# Arduino_Lego_Tank.net
KiCad netlist of a schematic drawn in EAGLE
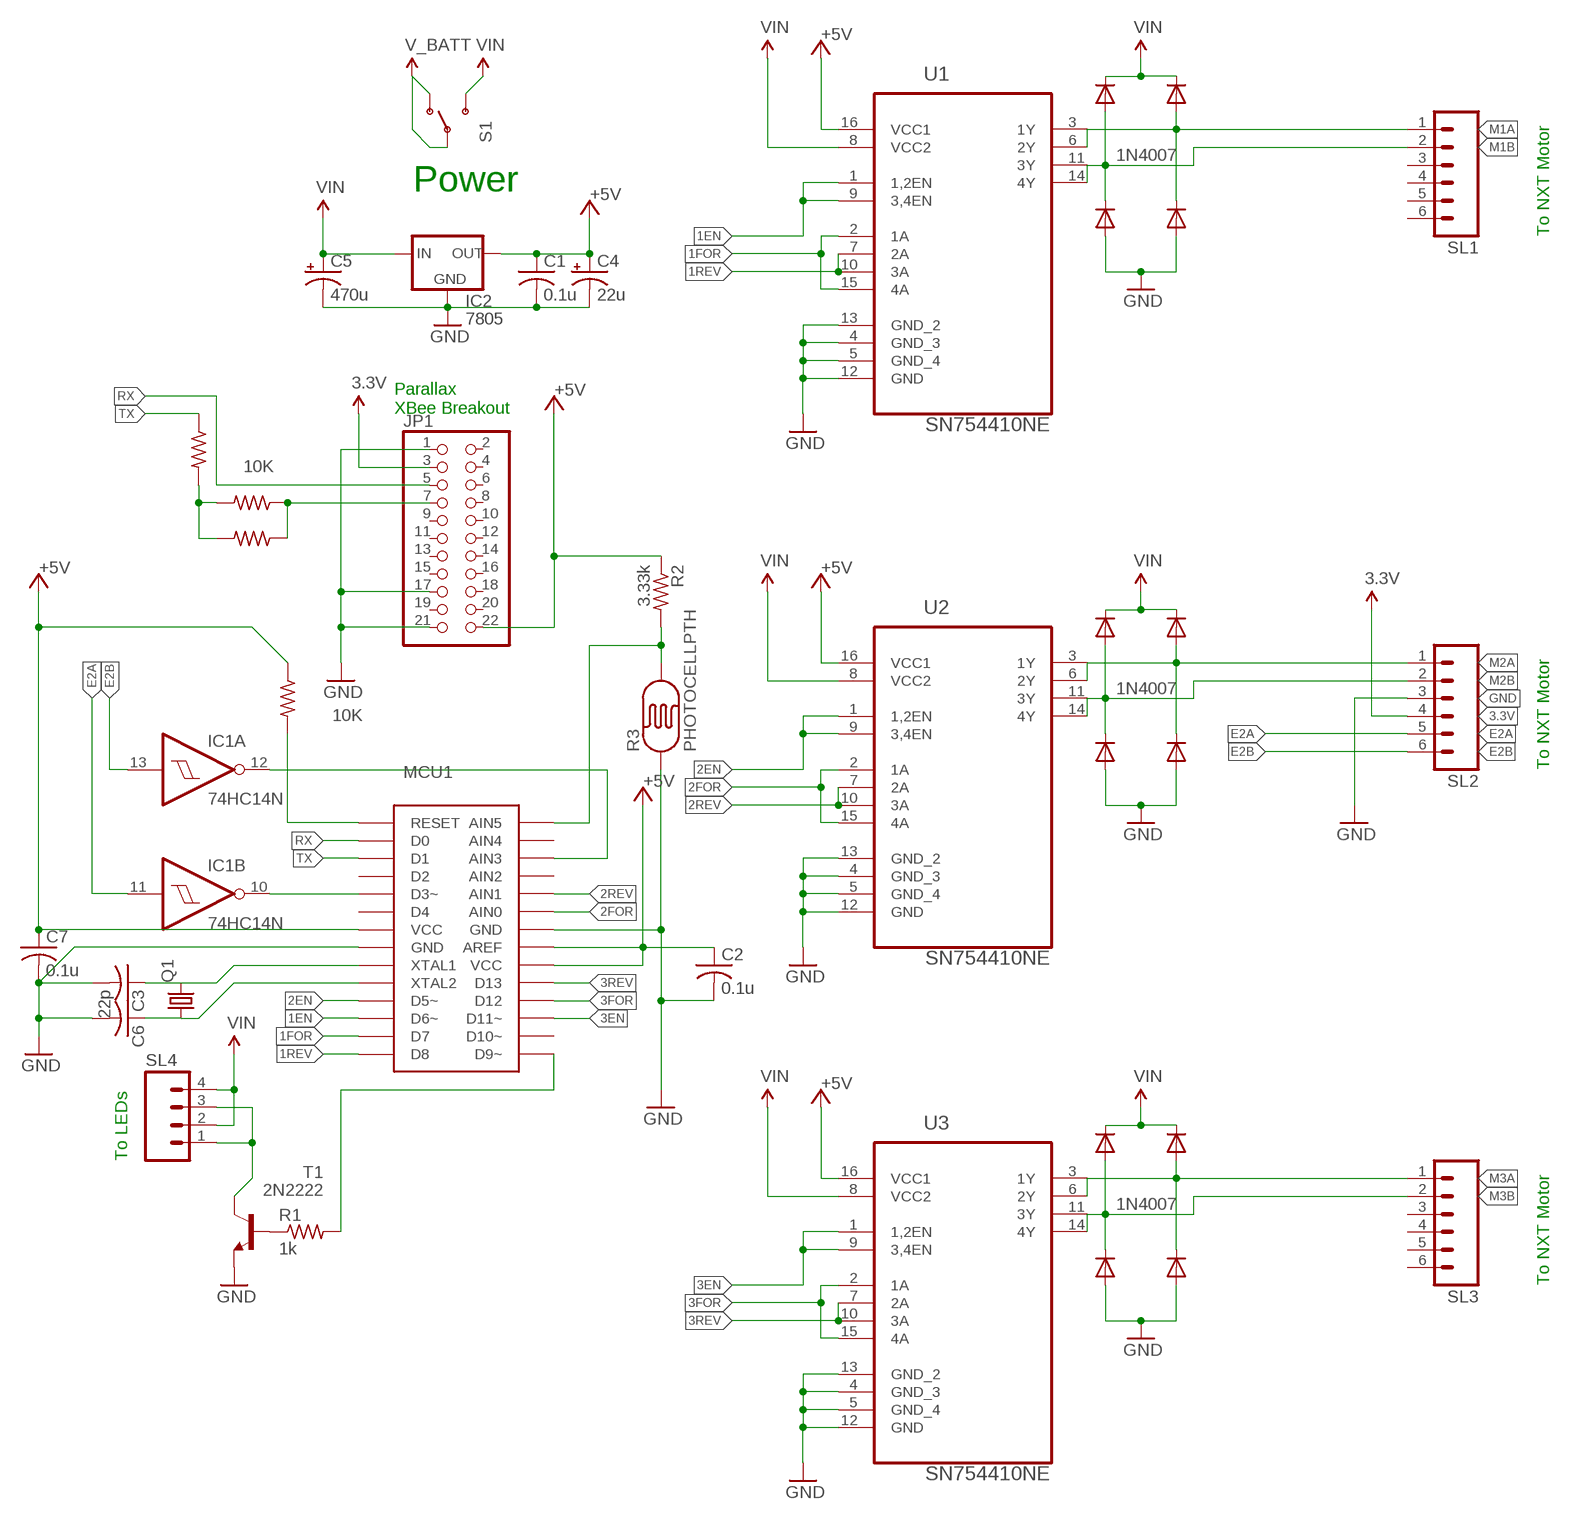
[diagram p0: schematic, sheet 1]

(export (version "E")
  (design (tool "Eeschema 10.0.6"))
  (components
    (comp (ref "C1")
      (value "0.1u")
      (footprint "eagle-import:C025-025X050")
      (libsource (lib "eagle-import") (part "C-US025-025X050"))
    )
    (comp (ref "C2")
      (value "0.1u")
      (footprint "eagle-import:C025-025X050")
      (libsource (lib "eagle-import") (part "C-US025-025X050"))
    )
    (comp (ref "C3")
      (value "22p")
      (footprint "eagle-import:C025-025X050")
      (libsource (lib "eagle-import") (part "C-US025-025X050"))
    )
    (comp (ref "C4")
      (value "22u")
      (footprint "eagle-import:E2,5-6")
      (libsource (lib "eagle-import") (part "CPOL-USE2.5-6"))
    )
    (comp (ref "C5")
      (value "470u")
      (footprint "eagle-import:E2,5-6")
      (libsource (lib "eagle-import") (part "CPOL-USE2.5-6"))
    )
    (comp (ref "C6")
      (value "C-US025-025X050")
      (footprint "eagle-import:C025-025X050")
      (libsource (lib "eagle-import") (part "C-US025-025X050"))
    )
    (comp (ref "C7")
      (value "0.1u")
      (footprint "eagle-import:C025-025X050")
      (libsource (lib "eagle-import") (part "C-US025-025X050"))
    )
    (comp (ref "D1")
      (value "1N4007")
      (footprint "eagle-import:DO41-10")
      (libsource (lib "eagle-import") (part "1N4004"))
    )
    (comp (ref "D2")
      (value "1N4007")
      (footprint "eagle-import:DO41-10")
      (libsource (lib "eagle-import") (part "1N4004"))
    )
    (comp (ref "D3")
      (value "1N4007")
      (footprint "eagle-import:DO41-10")
      (libsource (lib "eagle-import") (part "1N4004"))
    )
    (comp (ref "D4")
      (value "1N4007")
      (footprint "eagle-import:DO41-10")
      (libsource (lib "eagle-import") (part "1N4004"))
    )
    (comp (ref "D5")
      (value "1N4007")
      (footprint "eagle-import:DO41-10")
      (libsource (lib "eagle-import") (part "1N4004"))
    )
    (comp (ref "D6")
      (value "1N4007")
      (footprint "eagle-import:DO41-10")
      (libsource (lib "eagle-import") (part "1N4004"))
    )
    (comp (ref "D7")
      (value "1N4007")
      (footprint "eagle-import:DO41-10")
      (libsource (lib "eagle-import") (part "1N4004"))
    )
    (comp (ref "D8")
      (value "1N4007")
      (footprint "eagle-import:DO41-10")
      (libsource (lib "eagle-import") (part "1N4004"))
    )
    (comp (ref "D9")
      (value "1N4007")
      (footprint "eagle-import:DO41-10")
      (libsource (lib "eagle-import") (part "1N4004"))
    )
    (comp (ref "D10")
      (value "1N4007")
      (footprint "eagle-import:DO41-10")
      (libsource (lib "eagle-import") (part "1N4004"))
    )
    (comp (ref "D11")
      (value "1N4007")
      (footprint "eagle-import:DO41-10")
      (libsource (lib "eagle-import") (part "1N4004"))
    )
    (comp (ref "D12")
      (value "1N4007")
      (footprint "eagle-import:DO41-10")
      (libsource (lib "eagle-import") (part "1N4004"))
    )
    (comp (ref "IC1")
      (value "74HC14N")
      (footprint "eagle-import:DIL14")
      (libsource (lib "eagle-import") (part "7414NHC"))
    )
    (comp (ref "IC2")
      (value "7805")
      (footprint "eagle-import:TO220-IGO")
      (libsource (lib "eagle-import") (part "V_REG_78XXSINK"))
    )
    (comp (ref "JP1")
      (value "PINHD-2X11")
      (footprint "eagle-import:2X11")
      (libsource (lib "eagle-import") (part "PINHD-2X11"))
    )
    (comp (ref "MCU1")
      (value "ATMEGA328P")
      (footprint "eagle-import:ATMEGA328P")
      (libsource (lib "eagle-import") (part "ATMEGA328P"))
    )
    (comp (ref "Q1")
      (value "CRYSTALHC49S")
      (footprint "eagle-import:HC49_S")
      (libsource (lib "eagle-import") (part "CRYSTALHC49S"))
    )
    (comp (ref "R1")
      (value "1k")
      (footprint "eagle-import:0204_7")
      (libsource (lib "eagle-import") (part "R-US_0204/7"))
    )
    (comp (ref "R2")
      (value "3.33k")
      (footprint "eagle-import:0204_7")
      (libsource (lib "eagle-import") (part "R-US_0204/7"))
    )
    (comp (ref "R3")
      (value "PHOTOCELLPTH")
      (footprint "eagle-import:PHOTOCELL")
      (libsource (lib "eagle-import") (part "PHOTOCELLPTH"))
    )
    (comp (ref "R4")
      (value "R-US_0204/7")
      (footprint "eagle-import:0204_7")
      (libsource (lib "eagle-import") (part "R-US_0204/7"))
    )
    (comp (ref "R5")
      (value "coy")
      (footprint "eagle-import:0204_7")
      (libsource (lib "eagle-import") (part "R-US_0204/7"))
    )
    (comp (ref "R6")
      (value "10K")
      (footprint "eagle-import:0204_7")
      (libsource (lib "eagle-import") (part "R-US_0204/7"))
    )
    (comp (ref "R7")
      (value "10K")
      (footprint "eagle-import:0204_7")
      (libsource (lib "eagle-import") (part "R-US_0204/7"))
    )
    (comp (ref "S1")
      (value "SWITCH-SPDTKIT")
      (footprint "eagle-import:SWITCH-SPDT_KIT")
      (libsource (lib "eagle-import") (part "SWITCH-SPDTKIT"))
    )
    (comp (ref "SL1")
      (value "M06")
      (footprint "eagle-import:06P")
      (libsource (lib "eagle-import") (part "M06"))
    )
    (comp (ref "SL2")
      (value "M06")
      (footprint "eagle-import:06P")
      (libsource (lib "eagle-import") (part "M06"))
    )
    (comp (ref "SL3")
      (value "M06")
      (footprint "eagle-import:06P")
      (libsource (lib "eagle-import") (part "M06"))
    )
    (comp (ref "SL4")
      (value "M04")
      (footprint "eagle-import:04P")
      (libsource (lib "eagle-import") (part "M04"))
    )
    (comp (ref "T1")
      (value "2N2222")
      (footprint "eagle-import:TO92-EBC-OVAL")
      (libsource (lib "eagle-import") (part "2N2222"))
    )
    (comp (ref "U1")
      (value "SN754410NE")
      (footprint "eagle-import:DIP254P762X508-16")
      (libsource (lib "eagle-import") (part "SN754410NE"))
    )
    (comp (ref "U2")
      (value "SN754410NE")
      (footprint "eagle-import:DIP254P762X508-16")
      (libsource (lib "eagle-import") (part "SN754410NE"))
    )
    (comp (ref "U3")
      (value "SN754410NE")
      (footprint "eagle-import:DIP254P762X508-16")
      (libsource (lib "eagle-import") (part "SN754410NE"))
    )
  )
  (nets
    (net (code "1") (name "+5V") (class "Default")
      (node (ref "C1") (pin "1") (pinfunction "1_1") (pintype "passive"))
      (node (ref "C2") (pin "1") (pinfunction "1_1") (pintype "passive"))
      (node (ref "C4") (pin "+") (pinfunction "+_+") (pintype "passive"))
      (node (ref "C7") (pin "1") (pinfunction "1_1") (pintype "passive"))
      (node (ref "IC2") (pin "OUT") (pinfunction "OUT_OUT") (pintype "output"))
      (node (ref "JP1") (pin "22") (pinfunction "22_22") (pintype "passive"))
      (node (ref "MCU1") (pin "AREF") (pinfunction "AREF_AREF") (pintype "input"))
      (node (ref "MCU1") (pin "VCC") (pinfunction "VCC_VCC") (pintype "power_in"))
      (node (ref "MCU1") (pin "VCC2") (pinfunction "VCC_VCC2") (pintype "power_in"))
      (node (ref "R2") (pin "1") (pinfunction "1_1") (pintype "passive"))
      (node (ref "R7") (pin "1") (pinfunction "1_1") (pintype "passive"))
      (node (ref "U1") (pin "16") (pinfunction "VCC1_16") (pintype "power_in"))
      (node (ref "U2") (pin "16") (pinfunction "VCC1_16") (pintype "power_in"))
      (node (ref "U3") (pin "16") (pinfunction "VCC1_16") (pintype "power_in"))
    )
    (net (code "2") (name "1EN") (class "Default")
      (node (ref "MCU1") (pin "D6~") (pinfunction "D6~{}_D6~") (pintype "bidirectional"))
      (node (ref "U1") (pin "1") (pinfunction "1,2EN_1") (pintype "input"))
      (node (ref "U1") (pin "9") (pinfunction "3,4EN_9") (pintype "input"))
    )
    (net (code "3") (name "1FOR") (class "Default")
      (node (ref "MCU1") (pin "D7") (pinfunction "D7_D7") (pintype "bidirectional"))
      (node (ref "U1") (pin "15") (pinfunction "4A_15") (pintype "input"))
      (node (ref "U1") (pin "2") (pinfunction "1A_2") (pintype "input"))
    )
    (net (code "4") (name "1REV") (class "Default")
      (node (ref "MCU1") (pin "D8") (pinfunction "D8_D8") (pintype "bidirectional"))
      (node (ref "U1") (pin "10") (pinfunction "3A_10") (pintype "input"))
      (node (ref "U1") (pin "7") (pinfunction "2A_7") (pintype "input"))
    )
    (net (code "5") (name "2EN") (class "Default")
      (node (ref "MCU1") (pin "D5~") (pinfunction "D5~{}_D5~") (pintype "bidirectional"))
      (node (ref "U2") (pin "1") (pinfunction "1,2EN_1") (pintype "input"))
      (node (ref "U2") (pin "9") (pinfunction "3,4EN_9") (pintype "input"))
    )
    (net (code "6") (name "2FOR") (class "Default")
      (node (ref "MCU1") (pin "AIN0") (pinfunction "AIN0_AIN0") (pintype "bidirectional"))
      (node (ref "U2") (pin "15") (pinfunction "4A_15") (pintype "input"))
      (node (ref "U2") (pin "2") (pinfunction "1A_2") (pintype "input"))
    )
    (net (code "7") (name "2REV") (class "Default")
      (node (ref "MCU1") (pin "AIN1") (pinfunction "AIN1_AIN1") (pintype "bidirectional"))
      (node (ref "U2") (pin "10") (pinfunction "3A_10") (pintype "input"))
      (node (ref "U2") (pin "7") (pinfunction "2A_7") (pintype "input"))
    )
    (net (code "8") (name "3.3V") (class "Default")
      (node (ref "JP1") (pin "3") (pinfunction "3_3") (pintype "passive"))
      (node (ref "SL2") (pin "4") (pinfunction "4_4") (pintype "passive"))
    )
    (net (code "9") (name "3EN") (class "Default")
      (node (ref "MCU1") (pin "D11~") (pinfunction "D11~{}_D11~") (pintype "bidirectional"))
      (node (ref "U3") (pin "1") (pinfunction "1,2EN_1") (pintype "input"))
      (node (ref "U3") (pin "9") (pinfunction "3,4EN_9") (pintype "input"))
    )
    (net (code "10") (name "3FOR") (class "Default")
      (node (ref "MCU1") (pin "D12") (pinfunction "D12_D12") (pintype "bidirectional"))
      (node (ref "U3") (pin "15") (pinfunction "4A_15") (pintype "input"))
      (node (ref "U3") (pin "2") (pinfunction "1A_2") (pintype "input"))
    )
    (net (code "11") (name "3REV") (class "Default")
      (node (ref "MCU1") (pin "D13") (pinfunction "D13_D13") (pintype "bidirectional"))
      (node (ref "U3") (pin "10") (pinfunction "3A_10") (pintype "input"))
      (node (ref "U3") (pin "7") (pinfunction "2A_7") (pintype "input"))
    )
    (net (code "12") (name "E2A") (class "Default")
      (node (ref "IC1") (pin "11") (pinfunction "I_11") (pintype "input"))
      (node (ref "SL2") (pin "5") (pinfunction "5_5") (pintype "passive"))
    )
    (net (code "13") (name "E2B") (class "Default")
      (node (ref "IC1") (pin "13") (pinfunction "I_13") (pintype "input"))
      (node (ref "SL2") (pin "6") (pinfunction "6_6") (pintype "passive"))
    )
    (net (code "14") (name "GND") (class "Default")
      (node (ref "C1") (pin "2") (pinfunction "2_2") (pintype "passive"))
      (node (ref "C2") (pin "2") (pinfunction "2_2") (pintype "passive"))
      (node (ref "C3") (pin "2") (pinfunction "2_2") (pintype "passive"))
      (node (ref "C4") (pin "-") (pinfunction "-_-") (pintype "passive"))
      (node (ref "C5") (pin "-") (pinfunction "-_-") (pintype "passive"))
      (node (ref "C6") (pin "2") (pinfunction "2_2") (pintype "passive"))
      (node (ref "C7") (pin "2") (pinfunction "2_2") (pintype "passive"))
      (node (ref "D11") (pin "A") (pinfunction "A_A") (pintype "passive"))
      (node (ref "D12") (pin "A") (pinfunction "A_A") (pintype "passive"))
      (node (ref "D3") (pin "A") (pinfunction "A_A") (pintype "passive"))
      (node (ref "D4") (pin "A") (pinfunction "A_A") (pintype "passive"))
      (node (ref "D7") (pin "A") (pinfunction "A_A") (pintype "passive"))
      (node (ref "D8") (pin "A") (pinfunction "A_A") (pintype "passive"))
      (node (ref "IC2") (pin "GND") (pinfunction "GND_GND") (pintype "input"))
      (node (ref "JP1") (pin "1") (pinfunction "1_1") (pintype "passive"))
      (node (ref "JP1") (pin "17") (pinfunction "17_17") (pintype "passive"))
      (node (ref "JP1") (pin "21") (pinfunction "21_21") (pintype "passive"))
      (node (ref "MCU1") (pin "GND") (pinfunction "GND_GND") (pintype "power_in"))
      (node (ref "MCU1") (pin "GND1") (pinfunction "GND_GND1") (pintype "power_in"))
      (node (ref "R3") (pin "1") (pinfunction "P$1_1") (pintype "bidirectional"))
      (node (ref "SL2") (pin "3") (pinfunction "3_3") (pintype "passive"))
      (node (ref "T1") (pin "E") (pinfunction "E_E") (pintype "passive"))
      (node (ref "U1") (pin "12") (pinfunction "GND_12") (pintype "passive"))
      (node (ref "U1") (pin "13") (pinfunction "GND_2_13") (pintype "passive"))
      (node (ref "U1") (pin "4") (pinfunction "GND_3_4") (pintype "passive"))
      (node (ref "U1") (pin "5") (pinfunction "GND_4_5") (pintype "passive"))
      (node (ref "U2") (pin "12") (pinfunction "GND_12") (pintype "passive"))
      (node (ref "U2") (pin "13") (pinfunction "GND_2_13") (pintype "passive"))
      (node (ref "U2") (pin "4") (pinfunction "GND_3_4") (pintype "passive"))
      (node (ref "U2") (pin "5") (pinfunction "GND_4_5") (pintype "passive"))
      (node (ref "U3") (pin "12") (pinfunction "GND_12") (pintype "passive"))
      (node (ref "U3") (pin "13") (pinfunction "GND_2_13") (pintype "passive"))
      (node (ref "U3") (pin "4") (pinfunction "GND_3_4") (pintype "passive"))
      (node (ref "U3") (pin "5") (pinfunction "GND_4_5") (pintype "passive"))
    )
    (net (code "15") (name "M1A") (class "Default")
      (node (ref "D2") (pin "A") (pinfunction "A_A") (pintype "passive"))
      (node (ref "D4") (pin "C") (pinfunction "C_C") (pintype "passive"))
      (node (ref "SL1") (pin "1") (pinfunction "1_1") (pintype "passive"))
      (node (ref "U1") (pin "3") (pinfunction "1Y_3") (pintype "output"))
      (node (ref "U1") (pin "6") (pinfunction "2Y_6") (pintype "output"))
    )
    (net (code "16") (name "M1B") (class "Default")
      (node (ref "D1") (pin "A") (pinfunction "A_A") (pintype "passive"))
      (node (ref "D3") (pin "C") (pinfunction "C_C") (pintype "passive"))
      (node (ref "SL1") (pin "2") (pinfunction "2_2") (pintype "passive"))
      (node (ref "U1") (pin "11") (pinfunction "3Y_11") (pintype "output"))
      (node (ref "U1") (pin "14") (pinfunction "4Y_14") (pintype "output"))
    )
    (net (code "17") (name "M2A") (class "Default")
      (node (ref "D6") (pin "A") (pinfunction "A_A") (pintype "passive"))
      (node (ref "D8") (pin "C") (pinfunction "C_C") (pintype "passive"))
      (node (ref "SL2") (pin "1") (pinfunction "1_1") (pintype "passive"))
      (node (ref "U2") (pin "3") (pinfunction "1Y_3") (pintype "output"))
      (node (ref "U2") (pin "6") (pinfunction "2Y_6") (pintype "output"))
    )
    (net (code "18") (name "M2B") (class "Default")
      (node (ref "D5") (pin "A") (pinfunction "A_A") (pintype "passive"))
      (node (ref "D7") (pin "C") (pinfunction "C_C") (pintype "passive"))
      (node (ref "SL2") (pin "2") (pinfunction "2_2") (pintype "passive"))
      (node (ref "U2") (pin "11") (pinfunction "3Y_11") (pintype "output"))
      (node (ref "U2") (pin "14") (pinfunction "4Y_14") (pintype "output"))
    )
    (net (code "19") (name "M3A") (class "Default")
      (node (ref "D10") (pin "A") (pinfunction "A_A") (pintype "passive"))
      (node (ref "D12") (pin "C") (pinfunction "C_C") (pintype "passive"))
      (node (ref "SL3") (pin "1") (pinfunction "1_1") (pintype "passive"))
      (node (ref "U3") (pin "3") (pinfunction "1Y_3") (pintype "output"))
      (node (ref "U3") (pin "6") (pinfunction "2Y_6") (pintype "output"))
    )
    (net (code "20") (name "M3B") (class "Default")
      (node (ref "D11") (pin "C") (pinfunction "C_C") (pintype "passive"))
      (node (ref "D9") (pin "A") (pinfunction "A_A") (pintype "passive"))
      (node (ref "SL3") (pin "2") (pinfunction "2_2") (pintype "passive"))
      (node (ref "U3") (pin "11") (pinfunction "3Y_11") (pintype "output"))
      (node (ref "U3") (pin "14") (pinfunction "4Y_14") (pintype "output"))
    )
    (net (code "21") (name "Net-(C3-Pad1)") (class "Default")
      (node (ref "C3") (pin "1") (pinfunction "1_1") (pintype "passive"))
      (node (ref "MCU1") (pin "XTAL1") (pinfunction "XTAL1_XTAL1") (pintype "bidirectional"))
      (node (ref "Q1") (pin "2") (pinfunction "2_2") (pintype "passive"))
    )
    (net (code "22") (name "Net-(C6-Pad1)") (class "Default")
      (node (ref "C6") (pin "1") (pinfunction "1_1") (pintype "passive"))
      (node (ref "MCU1") (pin "XTAL2") (pinfunction "XTAL2_XTAL2") (pintype "bidirectional"))
      (node (ref "Q1") (pin "1") (pinfunction "1_1") (pintype "passive"))
    )
    (net (code "23") (name "Net-(IC1A-O)") (class "Default")
      (node (ref "IC1") (pin "12") (pinfunction "O_12") (pintype "output"))
      (node (ref "MCU1") (pin "AIN3") (pinfunction "AIN3_AIN3") (pintype "bidirectional"))
    )
    (net (code "24") (name "Net-(IC1B-O)") (class "Default")
      (node (ref "IC1") (pin "10") (pinfunction "O_10") (pintype "output"))
      (node (ref "MCU1") (pin "D3~") (pinfunction "D3~{}_D3~") (pintype "bidirectional"))
    )
    (net (code "25") (name "Net-(JP1-Pad7)") (class "Default")
      (node (ref "JP1") (pin "7") (pinfunction "7_7") (pintype "passive"))
      (node (ref "R4") (pin "1") (pinfunction "1_1") (pintype "passive"))
      (node (ref "R5") (pin "1") (pinfunction "1_1") (pintype "passive"))
    )
    (net (code "26") (name "Net-(MCU1-D9~{})") (class "Default")
      (node (ref "MCU1") (pin "D9~") (pinfunction "D9~{}_D9~") (pintype "bidirectional"))
      (node (ref "R1") (pin "2") (pinfunction "2_2") (pintype "passive"))
    )
    (net (code "27") (name "Net-(MCU1-PadRESET)") (class "Default")
      (node (ref "MCU1") (pin "RESET") (pinfunction "RESET_RESET") (pintype "input"))
      (node (ref "R7") (pin "2") (pinfunction "2_2") (pintype "passive"))
    )
    (net (code "28") (name "Net-(R1-Pad1)") (class "Default")
      (node (ref "R1") (pin "1") (pinfunction "1_1") (pintype "passive"))
      (node (ref "T1") (pin "B") (pinfunction "B_B") (pintype "passive"))
    )
    (net (code "29") (name "Net-(R3-P$2)") (class "Default")
      (node (ref "MCU1") (pin "AIN5") (pinfunction "AIN5_AIN5") (pintype "bidirectional"))
      (node (ref "R2") (pin "2") (pinfunction "2_2") (pintype "passive"))
      (node (ref "R3") (pin "2") (pinfunction "P$2_2") (pintype "bidirectional"))
    )
    (net (code "30") (name "Net-(R4-Pad2)") (class "Default")
      (node (ref "R4") (pin "2") (pinfunction "2_2") (pintype "passive"))
      (node (ref "R5") (pin "2") (pinfunction "2_2") (pintype "passive"))
      (node (ref "R6") (pin "2") (pinfunction "2_2") (pintype "passive"))
    )
    (net (code "31") (name "Net-(SL4-Pad1)") (class "Default")
      (node (ref "SL4") (pin "1") (pinfunction "1_1") (pintype "passive"))
      (node (ref "SL4") (pin "3") (pinfunction "3_3") (pintype "passive"))
      (node (ref "T1") (pin "C") (pinfunction "C_C") (pintype "passive"))
    )
    (net (code "32") (name "RX") (class "Default")
      (node (ref "JP1") (pin "5") (pinfunction "5_5") (pintype "passive"))
      (node (ref "MCU1") (pin "D0") (pinfunction "D0_D0") (pintype "bidirectional"))
    )
    (net (code "33") (name "TX") (class "Default")
      (node (ref "MCU1") (pin "D1") (pinfunction "D1_D1") (pintype "bidirectional"))
      (node (ref "R6") (pin "1") (pinfunction "1_1") (pintype "passive"))
    )
    (net (code "34") (name "VIN") (class "Default")
      (node (ref "C5") (pin "+") (pinfunction "+_+") (pintype "passive"))
      (node (ref "D1") (pin "C") (pinfunction "C_C") (pintype "passive"))
      (node (ref "D10") (pin "C") (pinfunction "C_C") (pintype "passive"))
      (node (ref "D2") (pin "C") (pinfunction "C_C") (pintype "passive"))
      (node (ref "D5") (pin "C") (pinfunction "C_C") (pintype "passive"))
      (node (ref "D6") (pin "C") (pinfunction "C_C") (pintype "passive"))
      (node (ref "D9") (pin "C") (pinfunction "C_C") (pintype "passive"))
      (node (ref "IC2") (pin "IN") (pinfunction "IN_IN") (pintype "input"))
      (node (ref "S1") (pin "3") (pinfunction "S_3") (pintype "passive"))
      (node (ref "SL4") (pin "2") (pinfunction "2_2") (pintype "passive"))
      (node (ref "SL4") (pin "4") (pinfunction "4_4") (pintype "passive"))
      (node (ref "U1") (pin "8") (pinfunction "VCC2_8") (pintype "power_in"))
      (node (ref "U2") (pin "8") (pinfunction "VCC2_8") (pintype "power_in"))
      (node (ref "U3") (pin "8") (pinfunction "VCC2_8") (pintype "power_in"))
    )
    (net (code "35") (name "V_BATT") (class "Default")
      (node (ref "S1") (pin "1") (pinfunction "O_1") (pintype "passive"))
      (node (ref "S1") (pin "2") (pinfunction "P_2") (pintype "passive"))
    )
    (net (code "36") (name "unconnected-(JP1-Pad2)") (class "Default")
      (node (ref "JP1") (pin "2") (pinfunction "2_2") (pintype "passive"))
    )
    (net (code "37") (name "unconnected-(JP1-Pad4)") (class "Default")
      (node (ref "JP1") (pin "4") (pinfunction "4_4") (pintype "passive"))
    )
    (net (code "38") (name "unconnected-(JP1-Pad6)") (class "Default")
      (node (ref "JP1") (pin "6") (pinfunction "6_6") (pintype "passive"))
    )
    (net (code "39") (name "unconnected-(JP1-Pad8)") (class "Default")
      (node (ref "JP1") (pin "8") (pinfunction "8_8") (pintype "passive"))
    )
    (net (code "40") (name "unconnected-(JP1-Pad9)") (class "Default")
      (node (ref "JP1") (pin "9") (pinfunction "9_9") (pintype "passive"))
    )
    (net (code "41") (name "unconnected-(JP1-Pad10)") (class "Default")
      (node (ref "JP1") (pin "10") (pinfunction "10_10") (pintype "passive"))
    )
    (net (code "42") (name "unconnected-(JP1-Pad11)") (class "Default")
      (node (ref "JP1") (pin "11") (pinfunction "11_11") (pintype "passive"))
    )
    (net (code "43") (name "unconnected-(JP1-Pad12)") (class "Default")
      (node (ref "JP1") (pin "12") (pinfunction "12_12") (pintype "passive"))
    )
    (net (code "44") (name "unconnected-(JP1-Pad13)") (class "Default")
      (node (ref "JP1") (pin "13") (pinfunction "13_13") (pintype "passive"))
    )
    (net (code "45") (name "unconnected-(JP1-Pad14)") (class "Default")
      (node (ref "JP1") (pin "14") (pinfunction "14_14") (pintype "passive"))
    )
    (net (code "46") (name "unconnected-(JP1-Pad15)") (class "Default")
      (node (ref "JP1") (pin "15") (pinfunction "15_15") (pintype "passive"))
    )
    (net (code "47") (name "unconnected-(JP1-Pad16)") (class "Default")
      (node (ref "JP1") (pin "16") (pinfunction "16_16") (pintype "passive"))
    )
    (net (code "48") (name "unconnected-(JP1-Pad18)") (class "Default")
      (node (ref "JP1") (pin "18") (pinfunction "18_18") (pintype "passive"))
    )
    (net (code "49") (name "unconnected-(JP1-Pad19)") (class "Default")
      (node (ref "JP1") (pin "19") (pinfunction "19_19") (pintype "passive"))
    )
    (net (code "50") (name "unconnected-(JP1-Pad20)") (class "Default")
      (node (ref "JP1") (pin "20") (pinfunction "20_20") (pintype "passive"))
    )
    (net (code "51") (name "unconnected-(MCU1-D10~{}-PadD10~)") (class "Default")
      (node (ref "MCU1") (pin "D10~") (pinfunction "D10~{}_D10~") (pintype "bidirectional"))
    )
    (net (code "52") (name "unconnected-(MCU1-PadAIN2)") (class "Default")
      (node (ref "MCU1") (pin "AIN2") (pinfunction "AIN2_AIN2") (pintype "bidirectional"))
    )
    (net (code "53") (name "unconnected-(MCU1-PadAIN4)") (class "Default")
      (node (ref "MCU1") (pin "AIN4") (pinfunction "AIN4_AIN4") (pintype "bidirectional"))
    )
    (net (code "54") (name "unconnected-(MCU1-PadD2)") (class "Default")
      (node (ref "MCU1") (pin "D2") (pinfunction "D2_D2") (pintype "bidirectional"))
    )
    (net (code "55") (name "unconnected-(MCU1-PadD4)") (class "Default")
      (node (ref "MCU1") (pin "D4") (pinfunction "D4_D4") (pintype "bidirectional"))
    )
    (net (code "56") (name "unconnected-(SL1-Pad3)") (class "Default")
      (node (ref "SL1") (pin "3") (pinfunction "3_3") (pintype "passive"))
    )
    (net (code "57") (name "unconnected-(SL1-Pad4)") (class "Default")
      (node (ref "SL1") (pin "4") (pinfunction "4_4") (pintype "passive"))
    )
    (net (code "58") (name "unconnected-(SL1-Pad5)") (class "Default")
      (node (ref "SL1") (pin "5") (pinfunction "5_5") (pintype "passive"))
    )
    (net (code "59") (name "unconnected-(SL1-Pad6)") (class "Default")
      (node (ref "SL1") (pin "6") (pinfunction "6_6") (pintype "passive"))
    )
    (net (code "60") (name "unconnected-(SL3-Pad3)") (class "Default")
      (node (ref "SL3") (pin "3") (pinfunction "3_3") (pintype "passive"))
    )
    (net (code "61") (name "unconnected-(SL3-Pad4)") (class "Default")
      (node (ref "SL3") (pin "4") (pinfunction "4_4") (pintype "passive"))
    )
    (net (code "62") (name "unconnected-(SL3-Pad5)") (class "Default")
      (node (ref "SL3") (pin "5") (pinfunction "5_5") (pintype "passive"))
    )
    (net (code "63") (name "unconnected-(SL3-Pad6)") (class "Default")
      (node (ref "SL3") (pin "6") (pinfunction "6_6") (pintype "passive"))
    )
  )
)
